# gas-sensor.net
KiCad netlist of a schematic drawn in EAGLE
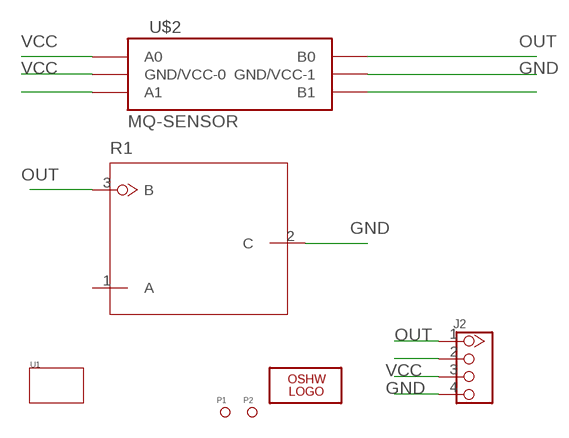
[diagram p0: schematic, sheet 1]

(export (version "E")
  (design (tool "Eeschema 10.0.6"))
  (components
    (comp (ref "J2")
      (value "TWIG-2.0-LEADED")
      (footprint "eagle-import:4P-LEADED-2.0")
      (libsource (lib "eagle-import") (part "TWIG-2.0-LEADED"))
    )
    (comp (ref "LOGO1")
      (value "LOGO-OSHW-FILLX0150-NT")
      (footprint "eagle-import:OSHW_FILLX150_NOTEXT")
      (libsource (lib "eagle-import") (part "LOGO-OSHW-FILLX0150-NT"))
    )
    (comp (ref "P1")
      (value "PAD-MARK")
      (footprint "eagle-import:ROUND-MARK-0.635")
      (libsource (lib "eagle-import") (part "PAD-MARK"))
    )
    (comp (ref "P2")
      (value "PAD-MARK")
      (footprint "eagle-import:ROUND-MARK-0.635")
      (libsource (lib "eagle-import") (part "PAD-MARK"))
    )
    (comp (ref "R1")
      (value "DEVICE_RESISTANCE")
      (footprint "eagle-import:PACKAGE__RESISTANCE")
      (libsource (lib "eagle-import") (part "DEVICE_RESISTANCE"))
    )
    (comp (ref "U$2")
      (value "MQ-SENSOR")
      (footprint "eagle-import:MQ-BASE")
      (libsource (lib "eagle-import") (part "MQ-SENSOR"))
    )
    (comp (ref "U1")
      (value "TWIG-2U")
      (footprint "eagle-import:2U-DIM-W_-DRILL")
      (libsource (lib "eagle-import") (part "TWIG-2U"))
    )
  )
  (nets
    (net (code "1") (name "/GND") (class "Default")
      (node (ref "J2") (pin "4") (pinfunction "4_4") (pintype "bidirectional"))
      (node (ref "R1") (pin "2") (pinfunction "C_2") (pintype "bidirectional"))
      (node (ref "U$2") (pin "HB") (pinfunction "GND/VCC-1_HB") (pintype "bidirectional"))
    )
    (net (code "2") (name "/OUT") (class "Default")
      (node (ref "J2") (pin "1") (pinfunction "1_1") (pintype "bidirectional"))
      (node (ref "R1") (pin "3") (pinfunction "B_3") (pintype "bidirectional"))
      (node (ref "U$2") (pin "B1") (pinfunction "B0_B1") (pintype "bidirectional"))
    )
    (net (code "3") (name "/VCC") (class "Default")
      (node (ref "J2") (pin "3") (pinfunction "3_3") (pintype "bidirectional"))
      (node (ref "U$2") (pin "A1") (pinfunction "A0_A1") (pintype "bidirectional"))
      (node (ref "U$2") (pin "HA") (pinfunction "GND/VCC-0_HA") (pintype "bidirectional"))
    )
    (net (code "4") (name "unconnected-(J2-Pad2)") (class "Default")
      (node (ref "J2") (pin "2") (pinfunction "2_2") (pintype "bidirectional"))
    )
    (net (code "5") (name "unconnected-(R1-A-Pad1)") (class "Default")
      (node (ref "R1") (pin "1") (pinfunction "A_1") (pintype "bidirectional"))
    )
    (net (code "6") (name "unconnected-(U$2-A1-PadA2)") (class "Default")
      (node (ref "U$2") (pin "A2") (pinfunction "A1_A2") (pintype "bidirectional"))
    )
    (net (code "7") (name "unconnected-(U$2-B1-PadB2)") (class "Default")
      (node (ref "U$2") (pin "B2") (pinfunction "B1_B2") (pintype "bidirectional"))
    )
  )
)
